# HEADERS_JHAT.net
KiCad netlist of a schematic drawn in Altium Designer
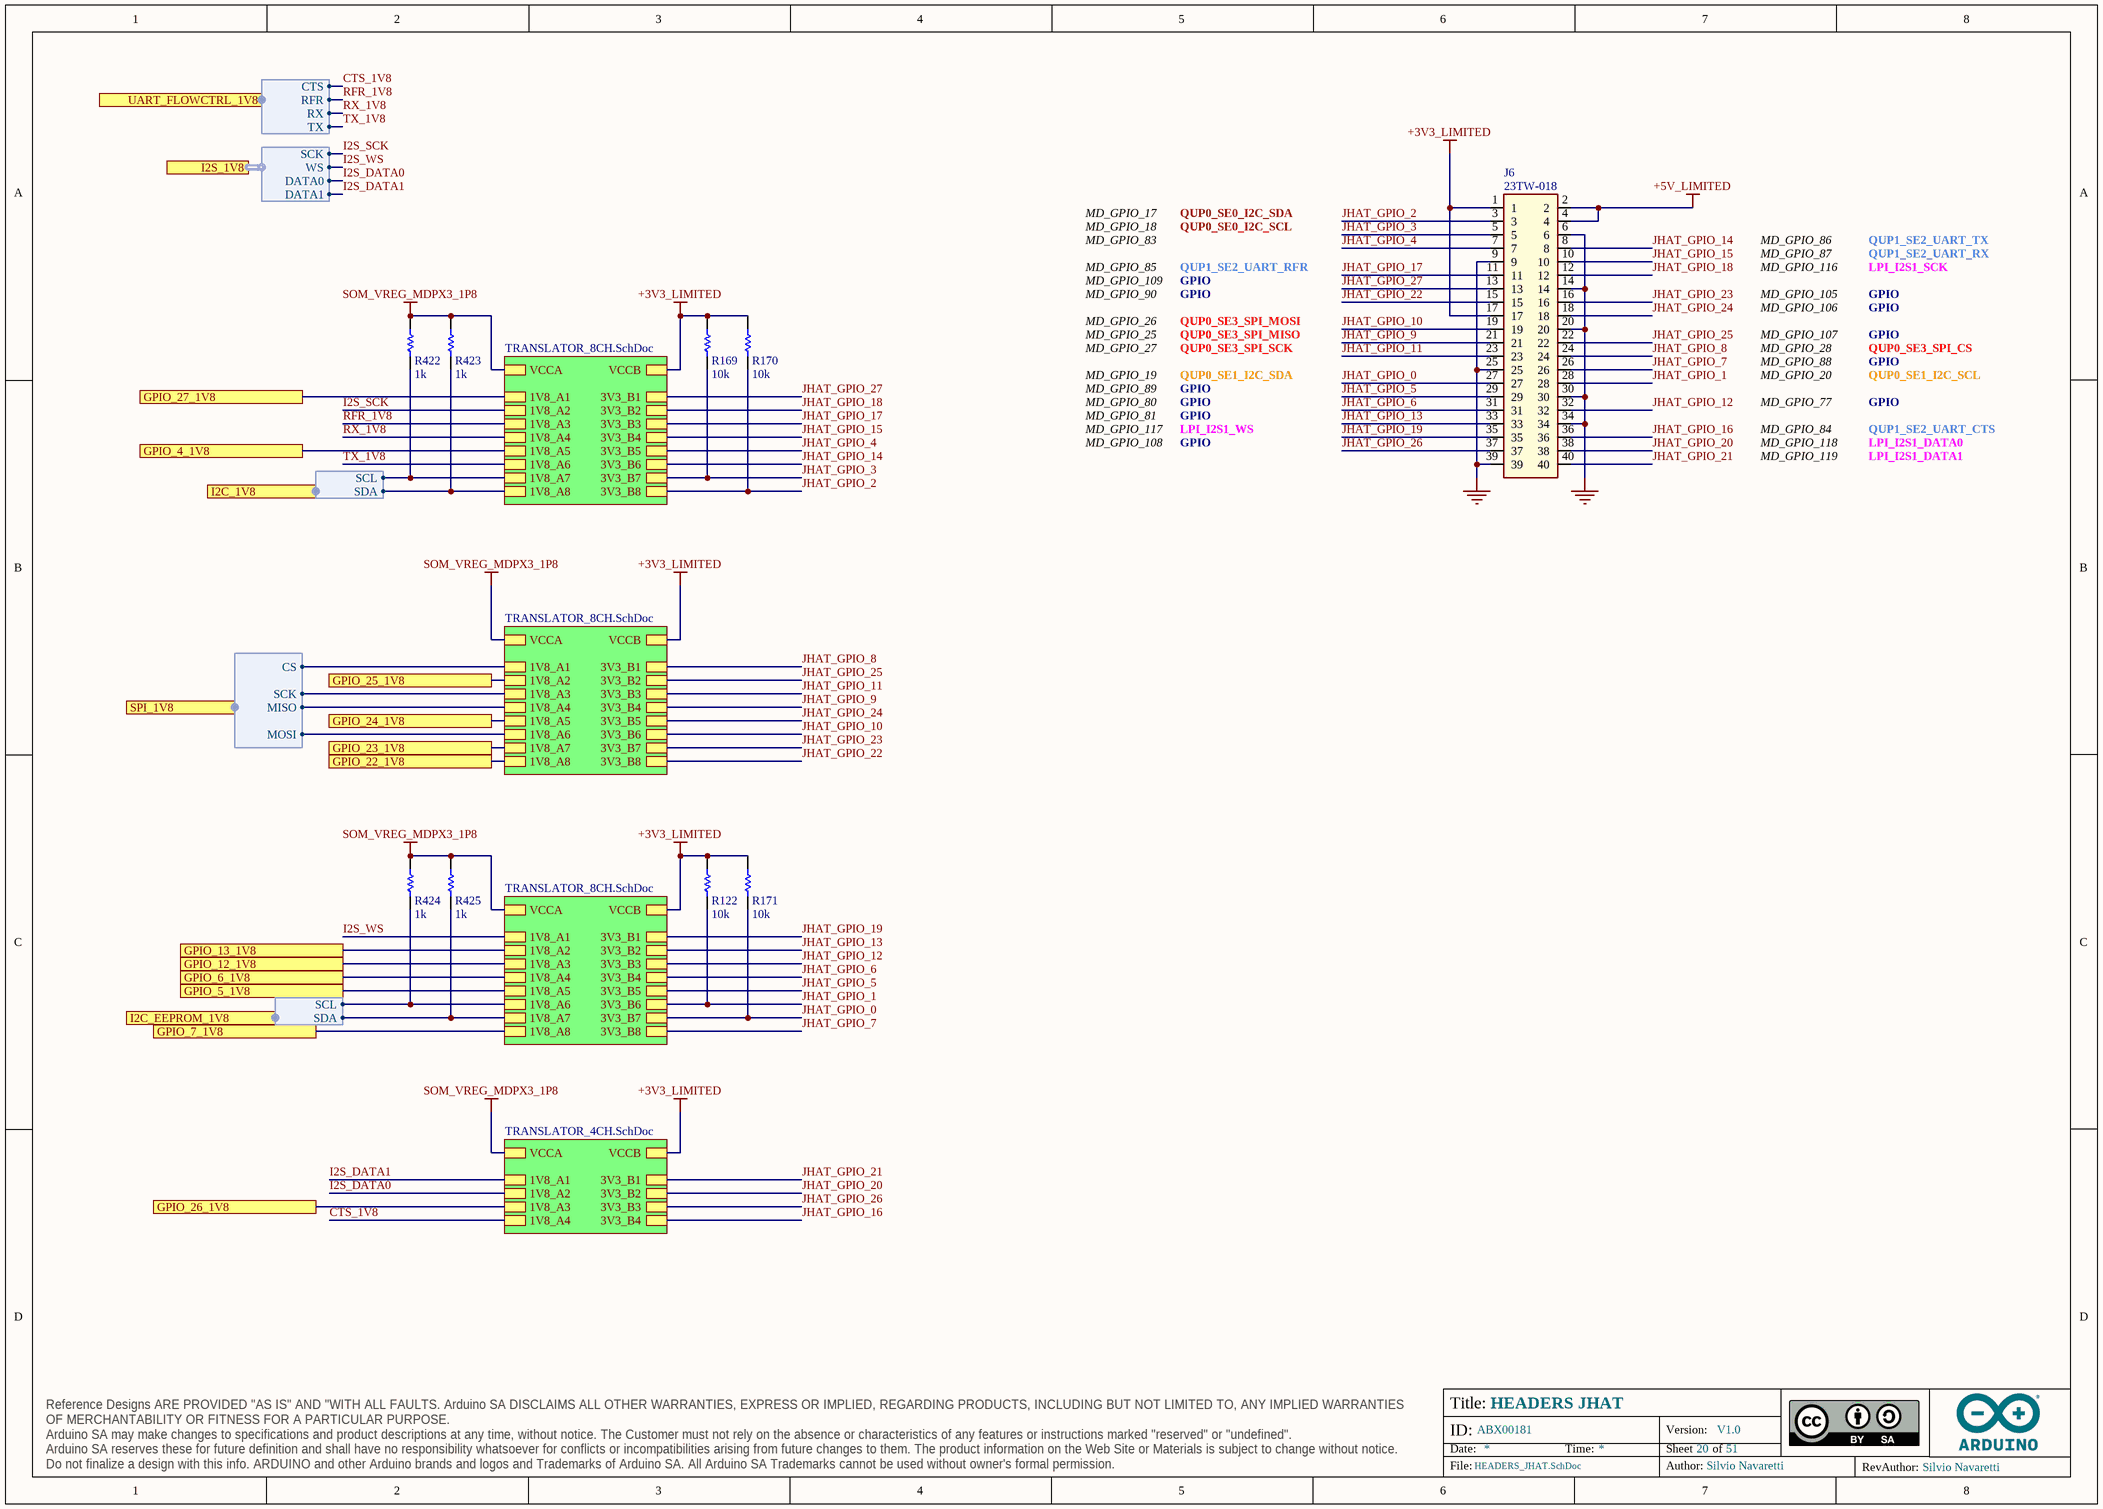
[diagram p0: HEADERS_JHAT.SchDoc]

(export (version "E")
  (design (tool "Eeschema 10.0.6"))
  (components
    (comp (ref "J6")
      (value "23TW-018")
      (footprint "23TW-018")
      (description "CONN HEADER MALE 40POS 2x20 2.54mm SMD 6mm pin length")
      (fields (field (name "MANUFACTURER") "4UCONN"))
      (libsource (lib "Clean") (part "23TW-018"))
    )
    (comp (ref "R122")
      (value "10k")
      (footprint "RES-0201")
      (description "RES CHIP 0201 10k 1% 1/20W")
      (fields (field (name "POWER") "50mW") (field (name "TOLERANCE") "1%"))
      (libsource (lib "Clean") (part "RES"))
    )
    (comp (ref "R169")
      (value "10k")
      (footprint "RES-0201")
      (description "RES CHIP 0201 10k 1% 1/20W")
      (fields (field (name "POWER") "50mW") (field (name "TOLERANCE") "1%"))
      (libsource (lib "Clean") (part "RES"))
    )
    (comp (ref "R170")
      (value "10k")
      (footprint "RES-0201")
      (description "RES CHIP 0201 10k 1% 1/20W")
      (fields (field (name "POWER") "50mW") (field (name "TOLERANCE") "1%"))
      (libsource (lib "Clean") (part "RES"))
    )
    (comp (ref "R171")
      (value "10k")
      (footprint "RES-0201")
      (description "RES CHIP 0201 10k 1% 1/20W")
      (fields (field (name "POWER") "50mW") (field (name "TOLERANCE") "1%"))
      (libsource (lib "Clean") (part "RES"))
    )
    (comp (ref "R422")
      (value "1k")
      (footprint "RES-0201")
      (description "RES CHIP 0201 1k 1% 1/20W")
      (fields (field (name "POWER") "50mW") (field (name "TOLERANCE") "1%"))
      (libsource (lib "Clean") (part "RES"))
    )
    (comp (ref "R423")
      (value "1k")
      (footprint "RES-0201")
      (description "RES CHIP 0201 1k 1% 1/20W")
      (fields (field (name "POWER") "50mW") (field (name "TOLERANCE") "1%"))
      (libsource (lib "Clean") (part "RES"))
    )
    (comp (ref "R424")
      (value "1k")
      (footprint "RES-0201")
      (description "RES CHIP 0201 1k 1% 1/20W")
      (fields (field (name "POWER") "50mW") (field (name "TOLERANCE") "1%"))
      (libsource (lib "Clean") (part "RES"))
    )
    (comp (ref "R425")
      (value "1k")
      (footprint "RES-0201")
      (description "RES CHIP 0201 1k 1% 1/20W")
      (fields (field (name "POWER") "50mW") (field (name "TOLERANCE") "1%"))
      (libsource (lib "Clean") (part "RES"))
    )
  )
  (nets
    (net (code "5") (name "+3V3_LIMITED") (class "Default")
      (node (ref "J6") (pin "1") (pinfunction "1_1") (pintype "passive"))
      (node (ref "J6") (pin "17") (pinfunction "17_17") (pintype "passive"))
      (node (ref "R122") (pin "1") (pinfunction "1_1") (pintype "passive"))
      (node (ref "R169") (pin "1") (pinfunction "1_1") (pintype "passive"))
      (node (ref "R170") (pin "1") (pinfunction "1_1") (pintype "passive"))
      (node (ref "R171") (pin "1") (pinfunction "1_1") (pintype "passive"))
    )
    (net (code "6") (name "+5V_LIMITED") (class "Default")
      (node (ref "J6") (pin "2") (pinfunction "2_2") (pintype "passive"))
      (node (ref "J6") (pin "4") (pinfunction "4_4") (pintype "passive"))
    )
    (net (code "10") (name "/1V8_A6") (class "Default")
      (node (ref "R424") (pin "2") (pinfunction "2_2") (pintype "passive"))
    )
    (net (code "12") (name "/1V8_A7") (class "Default")
      (node (ref "R425") (pin "2") (pinfunction "2_2") (pintype "passive"))
    )
    (net (code "13") (name "/1V8_A7_1") (class "Default")
      (node (ref "R422") (pin "2") (pinfunction "2_2") (pintype "passive"))
    )
    (net (code "14") (name "/1V8_A8") (class "Default")
      (node (ref "R423") (pin "2") (pinfunction "2_2") (pintype "passive"))
    )
    (net (code "32") (name "/JHAT_GPIO_0") (class "Default")
      (node (ref "J6") (pin "27") (pinfunction "27_27") (pintype "passive"))
      (node (ref "R171") (pin "2") (pinfunction "2_2") (pintype "passive"))
    )
    (net (code "33") (name "/JHAT_GPIO_1") (class "Default")
      (node (ref "J6") (pin "28") (pinfunction "28_28") (pintype "passive"))
      (node (ref "R122") (pin "2") (pinfunction "2_2") (pintype "passive"))
    )
    (net (code "34") (name "/JHAT_GPIO_2") (class "Default")
      (node (ref "J6") (pin "3") (pinfunction "3_3") (pintype "passive"))
      (node (ref "R170") (pin "2") (pinfunction "2_2") (pintype "passive"))
    )
    (net (code "35") (name "/JHAT_GPIO_3") (class "Default")
      (node (ref "J6") (pin "5") (pinfunction "5_5") (pintype "passive"))
      (node (ref "R169") (pin "2") (pinfunction "2_2") (pintype "passive"))
    )
    (net (code "36") (name "/JHAT_GPIO_4") (class "Default")
      (node (ref "J6") (pin "7") (pinfunction "7_7") (pintype "passive"))
    )
    (net (code "37") (name "/JHAT_GPIO_5") (class "Default")
      (node (ref "J6") (pin "29") (pinfunction "29_29") (pintype "passive"))
    )
    (net (code "38") (name "/JHAT_GPIO_6") (class "Default")
      (node (ref "J6") (pin "31") (pinfunction "31_31") (pintype "passive"))
    )
    (net (code "39") (name "/JHAT_GPIO_7") (class "Default")
      (node (ref "J6") (pin "26") (pinfunction "26_26") (pintype "passive"))
    )
    (net (code "40") (name "/JHAT_GPIO_8") (class "Default")
      (node (ref "J6") (pin "24") (pinfunction "24_24") (pintype "passive"))
    )
    (net (code "41") (name "/JHAT_GPIO_9") (class "Default")
      (node (ref "J6") (pin "21") (pinfunction "21_21") (pintype "passive"))
    )
    (net (code "42") (name "/JHAT_GPIO_10") (class "Default")
      (node (ref "J6") (pin "19") (pinfunction "19_19") (pintype "passive"))
    )
    (net (code "43") (name "/JHAT_GPIO_11") (class "Default")
      (node (ref "J6") (pin "23") (pinfunction "23_23") (pintype "passive"))
    )
    (net (code "44") (name "/JHAT_GPIO_12") (class "Default")
      (node (ref "J6") (pin "32") (pinfunction "32_32") (pintype "passive"))
    )
    (net (code "45") (name "/JHAT_GPIO_13") (class "Default")
      (node (ref "J6") (pin "33") (pinfunction "33_33") (pintype "passive"))
    )
    (net (code "46") (name "/JHAT_GPIO_14") (class "Default")
      (node (ref "J6") (pin "8") (pinfunction "8_8") (pintype "passive"))
    )
    (net (code "47") (name "/JHAT_GPIO_15") (class "Default")
      (node (ref "J6") (pin "10") (pinfunction "10_10") (pintype "passive"))
    )
    (net (code "48") (name "/JHAT_GPIO_16") (class "Default")
      (node (ref "J6") (pin "36") (pinfunction "36_36") (pintype "passive"))
    )
    (net (code "49") (name "/JHAT_GPIO_17") (class "Default")
      (node (ref "J6") (pin "11") (pinfunction "11_11") (pintype "passive"))
    )
    (net (code "50") (name "/JHAT_GPIO_18") (class "Default")
      (node (ref "J6") (pin "12") (pinfunction "12_12") (pintype "passive"))
    )
    (net (code "51") (name "/JHAT_GPIO_19") (class "Default")
      (node (ref "J6") (pin "35") (pinfunction "35_35") (pintype "passive"))
    )
    (net (code "52") (name "/JHAT_GPIO_20") (class "Default")
      (node (ref "J6") (pin "38") (pinfunction "38_38") (pintype "passive"))
    )
    (net (code "53") (name "/JHAT_GPIO_21") (class "Default")
      (node (ref "J6") (pin "40") (pinfunction "40_40") (pintype "passive"))
    )
    (net (code "54") (name "/JHAT_GPIO_22") (class "Default")
      (node (ref "J6") (pin "15") (pinfunction "15_15") (pintype "passive"))
    )
    (net (code "55") (name "/JHAT_GPIO_23") (class "Default")
      (node (ref "J6") (pin "16") (pinfunction "16_16") (pintype "passive"))
    )
    (net (code "56") (name "/JHAT_GPIO_24") (class "Default")
      (node (ref "J6") (pin "18") (pinfunction "18_18") (pintype "passive"))
    )
    (net (code "57") (name "/JHAT_GPIO_25") (class "Default")
      (node (ref "J6") (pin "22") (pinfunction "22_22") (pintype "passive"))
    )
    (net (code "58") (name "/JHAT_GPIO_26") (class "Default")
      (node (ref "J6") (pin "37") (pinfunction "37_37") (pintype "passive"))
    )
    (net (code "59") (name "/JHAT_GPIO_27") (class "Default")
      (node (ref "J6") (pin "13") (pinfunction "13_13") (pintype "passive"))
    )
    (net (code "67") (name "GND") (class "Default")
      (node (ref "J6") (pin "14") (pinfunction "14_14") (pintype "passive"))
      (node (ref "J6") (pin "20") (pinfunction "20_20") (pintype "passive"))
      (node (ref "J6") (pin "25") (pinfunction "25_25") (pintype "passive"))
      (node (ref "J6") (pin "30") (pinfunction "30_30") (pintype "passive"))
      (node (ref "J6") (pin "34") (pinfunction "34_34") (pintype "passive"))
      (node (ref "J6") (pin "39") (pinfunction "39_39") (pintype "passive"))
      (node (ref "J6") (pin "6") (pinfunction "6_6") (pintype "passive"))
      (node (ref "J6") (pin "9") (pinfunction "9_9") (pintype "passive"))
    )
    (net (code "68") (name "SOM_VREG_MDPX3_1P8") (class "Default")
      (node (ref "R422") (pin "1") (pinfunction "1_1") (pintype "passive"))
      (node (ref "R423") (pin "1") (pinfunction "1_1") (pintype "passive"))
      (node (ref "R424") (pin "1") (pinfunction "1_1") (pintype "passive"))
      (node (ref "R425") (pin "1") (pinfunction "1_1") (pintype "passive"))
    )
  )
)
